# nanoSTM32.net
KiCad netlist of a schematic drawn in Altium Designer
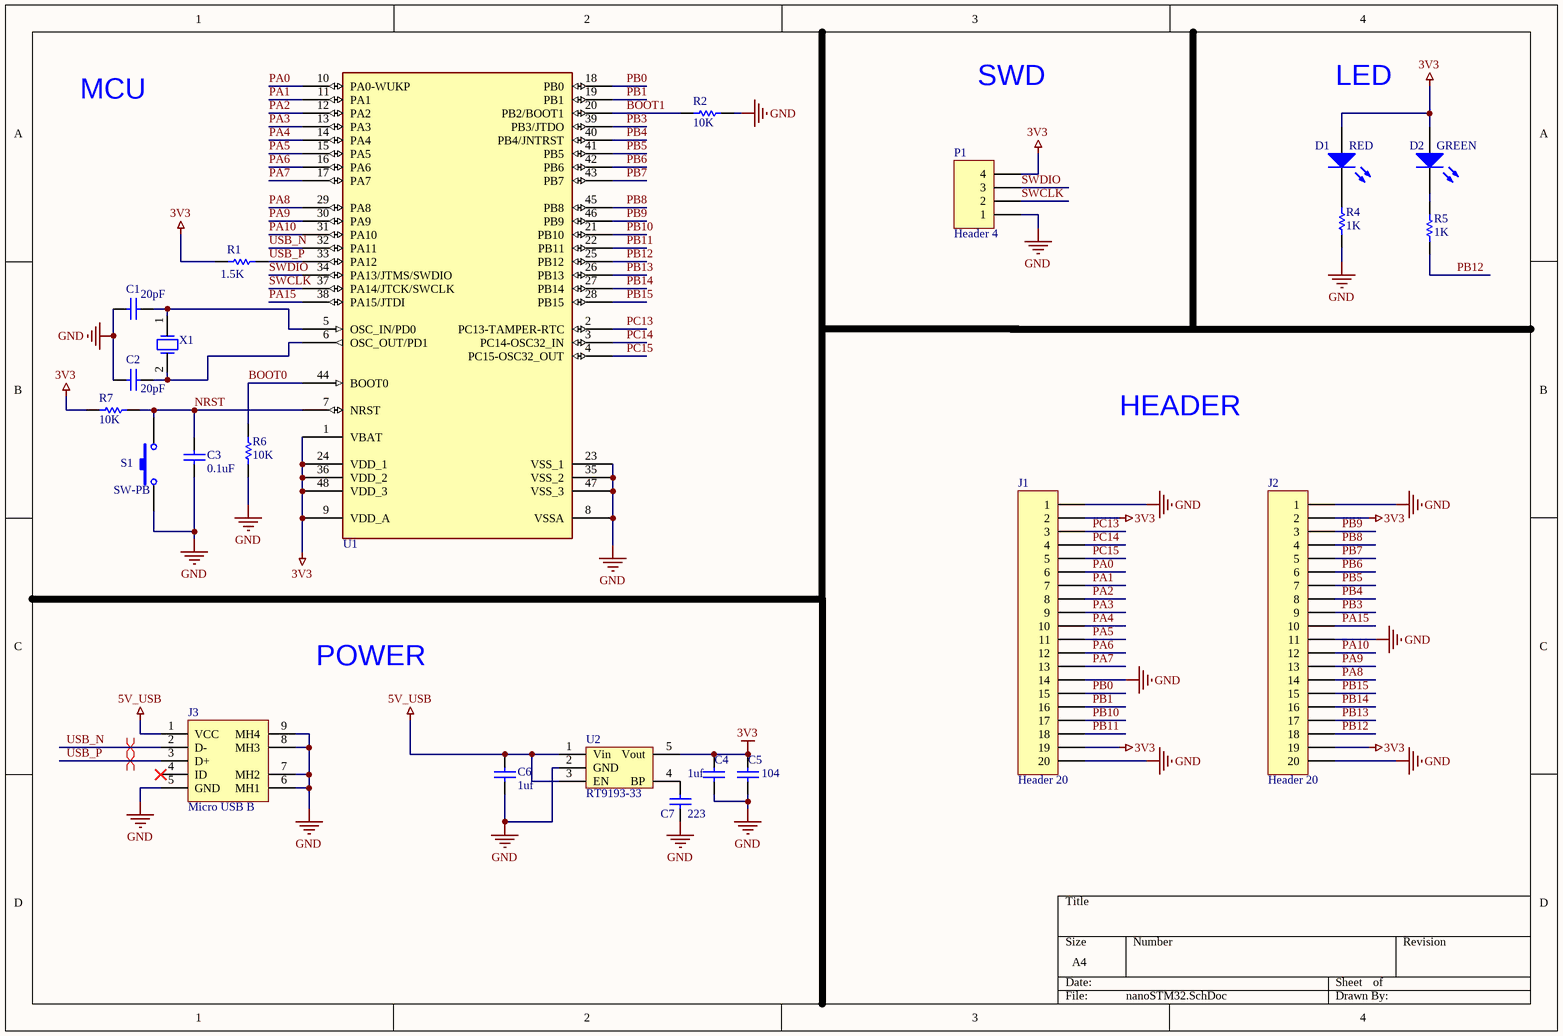
[diagram p0: nanoSTM32.SchDoc]

(export (version "E")
  (design (tool "Eeschema 10.0.6"))
  (components
    (comp (ref "C1")
      (value "20pF")
      (footprint "0603_C")
      (description "Capacitor")
      (fields (field (name "Comment") "C0603") (field (name "PUBLISHER") "Altium Limited"))
      (libsource (lib "MYLIB") (part "C-RAD-0603"))
    )
    (comp (ref "C2")
      (value "20pF")
      (footprint "0603_C")
      (description "Capacitor")
      (fields (field (name "Comment") "C0603") (field (name "PUBLISHER") "Altium Limited"))
      (libsource (lib "MYLIB") (part "C-RAD-0603"))
    )
    (comp (ref "C3")
      (value "0.1uF")
      (footprint "0603_C")
      (description "Capacitor")
      (fields (field (name "Comment") "C0603") (field (name "PUBLISHER") "Altium Limited"))
      (libsource (lib "MYLIB") (part "C-RAD-0603"))
    )
    (comp (ref "C4")
      (value "1uf")
      (footprint "0603_C")
      (description "Capacitor")
      (libsource (lib "Cheetie Integrated Library 2017") (part "CAP"))
    )
    (comp (ref "C5")
      (value "104")
      (footprint "0603_C")
      (description "Capacitor")
      (libsource (lib "Cheetie Integrated Library 2017") (part "CAP"))
    )
    (comp (ref "C6")
      (value "1uf")
      (footprint "0603_C")
      (description "Capacitor")
      (libsource (lib "Cheetie Integrated Library 2017") (part "CAP"))
    )
    (comp (ref "C7")
      (value "223")
      (footprint "0603_C")
      (description "Capacitor")
      (libsource (lib "Cheetie Integrated Library 2017") (part "CAP"))
    )
    (comp (ref "D1")
      (value "RED")
      (footprint "0603_LED")
      (description "Typical RED, GREEN, YELLOW, AMBER GaAs LED")
      (fields (field (name "PUBLISHER") "Altium Limited"))
      (libsource (lib "MYLIB") (part "D0603"))
    )
    (comp (ref "D2")
      (value "GREEN")
      (footprint "0603_LED")
      (description "Typical RED, GREEN, YELLOW, AMBER GaAs LED")
      (fields (field (name "PUBLISHER") "Altium Limited"))
      (libsource (lib "MYLIB") (part "D0603"))
    )
    (comp (ref "J1")
      (value "Header 20")
      (footprint "HEADER_20x1")
      (libsource (lib "nanoSTM32") (part "Header 20"))
    )
    (comp (ref "J2")
      (value "Header 20")
      (footprint "HEADER_20x1")
      (libsource (lib "nanoSTM32") (part "Header 20"))
    )
    (comp (ref "J3")
      (value "Micro USB B")
      (footprint "MICRO_USB")
      (libsource (lib "nanoSTM32") (part "Micro USB B"))
    )
    (comp (ref "logo") (value "logo") (libsource (lib "nanoSTM32") (part "logo")))
    (comp (ref "P1")
      (value "Header 4")
      (footprint "HEADER_4x1")
      (description "Header, 4-Pin")
      (fields (field (name "PUBLISHER") "Altium Limited"))
      (libsource (lib "Miscellaneous Connectors") (part "Header 4"))
    )
    (comp (ref "R1")
      (value "1.5K")
      (footprint "0603_R")
      (description "Resistor")
      (fields (field (name "Comment") "R0603") (field (name "PUBLISHER") "Altium Limited"))
      (libsource (lib "MYLIB") (part "0603-1"))
    )
    (comp (ref "R2")
      (value "10K")
      (footprint "0603_R")
      (description "Resistor")
      (fields (field (name "Comment") "R0603") (field (name "PUBLISHER") "Altium Limited"))
      (libsource (lib "MYLIB") (part "R0603"))
    )
    (comp (ref "R4")
      (value "1K")
      (footprint "0603_R")
      (description "Resistor")
      (fields (field (name "Comment") "R0603") (field (name "PUBLISHER") "Altium Limited"))
      (libsource (lib "MYLIB") (part "0603-1"))
    )
    (comp (ref "R5")
      (value "1K")
      (footprint "0603_R")
      (description "Resistor")
      (fields (field (name "Comment") "R0603") (field (name "PUBLISHER") "Altium Limited"))
      (libsource (lib "MYLIB") (part "0603-1"))
    )
    (comp (ref "R6")
      (value "10K")
      (footprint "0603_R")
      (description "Resistor")
      (fields (field (name "Comment") "R0603") (field (name "PUBLISHER") "Altium Limited"))
      (libsource (lib "MYLIB") (part "0603-1"))
    )
    (comp (ref "R7")
      (value "10K")
      (footprint "0603_R")
      (description "Resistor")
      (fields (field (name "Comment") "R0603") (field (name "PUBLISHER") "Altium Limited"))
      (libsource (lib "MYLIB") (part "0603-1"))
    )
    (comp (ref "S1")
      (value "SW-PB")
      (footprint "SMT_SW_PTS_820")
      (description "Switch")
      (fields (field (name "PUBLISHER") "Altium Limited"))
      (libsource (lib "Miscellaneous Devices") (part "SW-PB"))
    )
    (comp (ref "U1")
      (value "STM32F103C8T6")
      (footprint "LQFP48_N")
      (description "LowPower MCU")
      (libsource (lib "MYLIB") (part "STM32F103C8T6"))
    )
    (comp (ref "U2")
      (value "RT9193-33")
      (footprint "SOT23-5")
      (libsource (lib "Cheetie Integrated Library 2017") (part "RT9193-33"))
    )
    (comp (ref "X1") (value "XTAL") (footprint "49SMD") (libsource (lib "MYLIB") (part "XTAL")))
  )
  (nets
    (net (code "1") (name "/BOOT0") (class "Default")
      (node (ref "R6") (pin "1") (pinfunction "1_1") (pintype "passive"))
      (node (ref "U1") (pin "44") (pinfunction "BOOT0_44") (pintype "input"))
    )
    (net (code "2") (name "/BOOT1") (class "Default")
      (node (ref "R2") (pin "2") (pinfunction "2_2") (pintype "passive"))
      (node (ref "U1") (pin "20") (pinfunction "PB2/BOOT1_20") (pintype "bidirectional"))
    )
    (net (code "3") (name "/NRST") (class "Default")
      (node (ref "C3") (pin "2") (pinfunction "2_2") (pintype "passive"))
      (node (ref "R7") (pin "1") (pinfunction "1_1") (pintype "passive"))
      (node (ref "S1") (pin "2") (pinfunction "2_2") (pintype "passive"))
      (node (ref "U1") (pin "7") (pinfunction "NRST_7") (pintype "bidirectional"))
    )
    (net (code "4") (name "/PA0") (class "Default")
      (node (ref "J1") (pin "6") (pinfunction "6_6") (pintype "passive"))
      (node (ref "U1") (pin "10") (pinfunction "PA0-WUKP_10") (pintype "bidirectional"))
    )
    (net (code "5") (name "/PA1") (class "Default")
      (node (ref "J1") (pin "7") (pinfunction "7_7") (pintype "passive"))
      (node (ref "U1") (pin "11") (pinfunction "PA1_11") (pintype "bidirectional"))
    )
    (net (code "6") (name "/PA2") (class "Default")
      (node (ref "J1") (pin "8") (pinfunction "8_8") (pintype "passive"))
      (node (ref "U1") (pin "12") (pinfunction "PA2_12") (pintype "bidirectional"))
    )
    (net (code "7") (name "/PA3") (class "Default")
      (node (ref "J1") (pin "9") (pinfunction "9_9") (pintype "passive"))
      (node (ref "U1") (pin "13") (pinfunction "PA3_13") (pintype "bidirectional"))
    )
    (net (code "8") (name "/PA4") (class "Default")
      (node (ref "J1") (pin "10") (pinfunction "10_10") (pintype "passive"))
      (node (ref "U1") (pin "14") (pinfunction "PA4_14") (pintype "bidirectional"))
    )
    (net (code "9") (name "/PA5") (class "Default")
      (node (ref "J1") (pin "11") (pinfunction "11_11") (pintype "passive"))
      (node (ref "U1") (pin "15") (pinfunction "PA5_15") (pintype "bidirectional"))
    )
    (net (code "10") (name "/PA6") (class "Default")
      (node (ref "J1") (pin "12") (pinfunction "12_12") (pintype "passive"))
      (node (ref "U1") (pin "16") (pinfunction "PA6_16") (pintype "bidirectional"))
    )
    (net (code "11") (name "/PA7") (class "Default")
      (node (ref "J1") (pin "13") (pinfunction "13_13") (pintype "passive"))
      (node (ref "U1") (pin "17") (pinfunction "PA7_17") (pintype "bidirectional"))
    )
    (net (code "12") (name "/PA8") (class "Default")
      (node (ref "J2") (pin "14") (pinfunction "14_14") (pintype "passive"))
      (node (ref "U1") (pin "29") (pinfunction "PA8_29") (pintype "bidirectional"))
    )
    (net (code "13") (name "/PA9") (class "Default")
      (node (ref "J2") (pin "13") (pinfunction "13_13") (pintype "passive"))
      (node (ref "U1") (pin "30") (pinfunction "PA9_30") (pintype "bidirectional"))
    )
    (net (code "14") (name "/PA10") (class "Default")
      (node (ref "J2") (pin "12") (pinfunction "12_12") (pintype "passive"))
      (node (ref "U1") (pin "31") (pinfunction "PA10_31") (pintype "bidirectional"))
    )
    (net (code "15") (name "/PA15") (class "Default")
      (node (ref "J2") (pin "10") (pinfunction "10_10") (pintype "passive"))
      (node (ref "U1") (pin "38") (pinfunction "PA15/JTDI_38") (pintype "bidirectional"))
    )
    (net (code "16") (name "/PB0") (class "Default")
      (node (ref "J1") (pin "15") (pinfunction "15_15") (pintype "passive"))
      (node (ref "U1") (pin "18") (pinfunction "PB0_18") (pintype "bidirectional"))
    )
    (net (code "17") (name "/PB1") (class "Default")
      (node (ref "J1") (pin "16") (pinfunction "16_16") (pintype "passive"))
      (node (ref "U1") (pin "19") (pinfunction "PB1_19") (pintype "bidirectional"))
    )
    (net (code "18") (name "/PB3") (class "Default")
      (node (ref "J2") (pin "9") (pinfunction "9_9") (pintype "passive"))
      (node (ref "U1") (pin "39") (pinfunction "PB3/JTDO_39") (pintype "bidirectional"))
    )
    (net (code "19") (name "/PB4") (class "Default")
      (node (ref "J2") (pin "8") (pinfunction "8_8") (pintype "passive"))
      (node (ref "U1") (pin "40") (pinfunction "PB4/JNTRST_40") (pintype "bidirectional"))
    )
    (net (code "20") (name "/PB5") (class "Default")
      (node (ref "J2") (pin "7") (pinfunction "7_7") (pintype "passive"))
      (node (ref "U1") (pin "41") (pinfunction "PB5_41") (pintype "bidirectional"))
    )
    (net (code "21") (name "/PB6") (class "Default")
      (node (ref "J2") (pin "6") (pinfunction "6_6") (pintype "passive"))
      (node (ref "U1") (pin "42") (pinfunction "PB6_42") (pintype "bidirectional"))
    )
    (net (code "22") (name "/PB7") (class "Default")
      (node (ref "J2") (pin "5") (pinfunction "5_5") (pintype "passive"))
      (node (ref "U1") (pin "43") (pinfunction "PB7_43") (pintype "bidirectional"))
    )
    (net (code "23") (name "/PB8") (class "Default")
      (node (ref "J2") (pin "4") (pinfunction "4_4") (pintype "passive"))
      (node (ref "U1") (pin "45") (pinfunction "PB8_45") (pintype "bidirectional"))
    )
    (net (code "24") (name "/PB9") (class "Default")
      (node (ref "J2") (pin "3") (pinfunction "3_3") (pintype "passive"))
      (node (ref "U1") (pin "46") (pinfunction "PB9_46") (pintype "bidirectional"))
    )
    (net (code "25") (name "/PB10") (class "Default")
      (node (ref "J1") (pin "17") (pinfunction "17_17") (pintype "passive"))
      (node (ref "U1") (pin "21") (pinfunction "PB10_21") (pintype "bidirectional"))
    )
    (net (code "26") (name "/PB11") (class "Default")
      (node (ref "J1") (pin "18") (pinfunction "18_18") (pintype "passive"))
      (node (ref "U1") (pin "22") (pinfunction "PB11_22") (pintype "bidirectional"))
    )
    (net (code "27") (name "/PB12") (class "Default")
      (node (ref "J2") (pin "18") (pinfunction "18_18") (pintype "passive"))
      (node (ref "R5") (pin "1") (pinfunction "1_1") (pintype "passive"))
      (node (ref "U1") (pin "25") (pinfunction "PB12_25") (pintype "bidirectional"))
    )
    (net (code "28") (name "/PB13") (class "Default")
      (node (ref "J2") (pin "17") (pinfunction "17_17") (pintype "passive"))
      (node (ref "U1") (pin "26") (pinfunction "PB13_26") (pintype "bidirectional"))
    )
    (net (code "29") (name "/PB14") (class "Default")
      (node (ref "J2") (pin "16") (pinfunction "16_16") (pintype "passive"))
      (node (ref "U1") (pin "27") (pinfunction "PB14_27") (pintype "bidirectional"))
    )
    (net (code "30") (name "/PB15") (class "Default")
      (node (ref "J2") (pin "15") (pinfunction "15_15") (pintype "passive"))
      (node (ref "U1") (pin "28") (pinfunction "PB15_28") (pintype "bidirectional"))
    )
    (net (code "31") (name "/PC13") (class "Default")
      (node (ref "J1") (pin "3") (pinfunction "3_3") (pintype "passive"))
      (node (ref "U1") (pin "2") (pinfunction "PC13-TAMPER-RTC_2") (pintype "bidirectional"))
    )
    (net (code "32") (name "/PC14") (class "Default")
      (node (ref "J1") (pin "4") (pinfunction "4_4") (pintype "passive"))
      (node (ref "U1") (pin "3") (pinfunction "PC14-OSC32_IN_3") (pintype "bidirectional"))
    )
    (net (code "33") (name "/PC15") (class "Default")
      (node (ref "J1") (pin "5") (pinfunction "5_5") (pintype "passive"))
      (node (ref "U1") (pin "4") (pinfunction "PC15-OSC32_OUT_4") (pintype "bidirectional"))
    )
    (net (code "34") (name "/SWCLK") (class "Default")
      (node (ref "P1") (pin "2") (pinfunction "2_2") (pintype "passive"))
      (node (ref "U1") (pin "37") (pinfunction "PA14/JTCK/SWCLK_37") (pintype "bidirectional"))
    )
    (net (code "35") (name "/SWDIO") (class "Default")
      (node (ref "P1") (pin "3") (pinfunction "3_3") (pintype "passive"))
      (node (ref "U1") (pin "34") (pinfunction "PA13/JTMS/SWDIO_34") (pintype "bidirectional"))
    )
    (net (code "36") (name "/USB_N") (class "Default")
      (node (ref "J3") (pin "2") (pinfunction "D-_2") (pintype "passive"))
      (node (ref "U1") (pin "32") (pinfunction "PA11_32") (pintype "bidirectional"))
    )
    (net (code "37") (name "/USB_P") (class "Default")
      (node (ref "J3") (pin "3") (pinfunction "D+_3") (pintype "passive"))
      (node (ref "R1") (pin "1") (pinfunction "1_1") (pintype "passive"))
      (node (ref "U1") (pin "33") (pinfunction "PA12_33") (pintype "bidirectional"))
    )
    (net (code "38") (name "3V3") (class "Default")
      (node (ref "C4") (pin "2") (pinfunction "2_2") (pintype "passive"))
      (node (ref "C5") (pin "2") (pinfunction "2_2") (pintype "passive"))
      (node (ref "D1") (pin "1") (pinfunction "A_1") (pintype "passive"))
      (node (ref "D2") (pin "1") (pinfunction "A_1") (pintype "passive"))
      (node (ref "J1") (pin "19") (pinfunction "19_19") (pintype "passive"))
      (node (ref "J1") (pin "2") (pinfunction "2_2") (pintype "passive"))
      (node (ref "J2") (pin "19") (pinfunction "19_19") (pintype "passive"))
      (node (ref "J2") (pin "2") (pinfunction "2_2") (pintype "passive"))
      (node (ref "P1") (pin "4") (pinfunction "4_4") (pintype "passive"))
      (node (ref "R1") (pin "2") (pinfunction "2_2") (pintype "passive"))
      (node (ref "R7") (pin "2") (pinfunction "2_2") (pintype "passive"))
      (node (ref "U1") (pin "1") (pinfunction "VBAT_1") (pintype "passive"))
      (node (ref "U1") (pin "24") (pinfunction "VDD_1_24") (pintype "passive"))
      (node (ref "U1") (pin "36") (pinfunction "VDD_2_36") (pintype "passive"))
      (node (ref "U1") (pin "48") (pinfunction "VDD_3_48") (pintype "passive"))
      (node (ref "U1") (pin "9") (pinfunction "VDD_A_9") (pintype "passive"))
      (node (ref "U2") (pin "5") (pinfunction "Vout_5") (pintype "passive"))
    )
    (net (code "39") (name "5V_USB") (class "Default")
      (node (ref "C6") (pin "2") (pinfunction "2_2") (pintype "passive"))
      (node (ref "J3") (pin "1") (pinfunction "VCC_1") (pintype "passive"))
      (node (ref "U2") (pin "1") (pinfunction "Vin_1") (pintype "passive"))
      (node (ref "U2") (pin "3") (pinfunction "EN_3") (pintype "passive"))
    )
    (net (code "40") (name "GND") (class "Default")
      (node (ref "C1") (pin "2") (pinfunction "2_2") (pintype "passive"))
      (node (ref "C2") (pin "2") (pinfunction "2_2") (pintype "passive"))
      (node (ref "C3") (pin "1") (pinfunction "1_1") (pintype "passive"))
      (node (ref "C4") (pin "1") (pinfunction "1_1") (pintype "passive"))
      (node (ref "C5") (pin "1") (pinfunction "1_1") (pintype "passive"))
      (node (ref "C6") (pin "1") (pinfunction "1_1") (pintype "passive"))
      (node (ref "C7") (pin "1") (pinfunction "1_1") (pintype "passive"))
      (node (ref "J1") (pin "1") (pinfunction "1_1") (pintype "passive"))
      (node (ref "J1") (pin "14") (pinfunction "14_14") (pintype "passive"))
      (node (ref "J1") (pin "20") (pinfunction "20_20") (pintype "passive"))
      (node (ref "J2") (pin "1") (pinfunction "1_1") (pintype "passive"))
      (node (ref "J2") (pin "11") (pinfunction "11_11") (pintype "passive"))
      (node (ref "J2") (pin "20") (pinfunction "20_20") (pintype "passive"))
      (node (ref "J3") (pin "5") (pinfunction "GND_5") (pintype "passive"))
      (node (ref "J3") (pin "6") (pinfunction "MH1_6") (pintype "passive"))
      (node (ref "J3") (pin "7") (pinfunction "MH2_7") (pintype "passive"))
      (node (ref "J3") (pin "8") (pinfunction "MH3_8") (pintype "passive"))
      (node (ref "J3") (pin "9") (pinfunction "MH4_9") (pintype "passive"))
      (node (ref "P1") (pin "1") (pinfunction "1_1") (pintype "passive"))
      (node (ref "R2") (pin "1") (pinfunction "1_1") (pintype "passive"))
      (node (ref "R4") (pin "1") (pinfunction "1_1") (pintype "passive"))
      (node (ref "R6") (pin "2") (pinfunction "2_2") (pintype "passive"))
      (node (ref "S1") (pin "1") (pinfunction "1_1") (pintype "passive"))
      (node (ref "U1") (pin "23") (pinfunction "VSS_1_23") (pintype "passive"))
      (node (ref "U1") (pin "35") (pinfunction "VSS_2_35") (pintype "passive"))
      (node (ref "U1") (pin "47") (pinfunction "VSS_3_47") (pintype "passive"))
      (node (ref "U1") (pin "8") (pinfunction "VSSA_8") (pintype "passive"))
      (node (ref "U2") (pin "2") (pinfunction "GND_2") (pintype "passive"))
    )
    (net (code "41") (name "Net-(D1-K)") (class "Default")
      (node (ref "D1") (pin "2") (pinfunction "K_2") (pintype "passive"))
      (node (ref "R4") (pin "2") (pinfunction "2_2") (pintype "passive"))
    )
    (net (code "42") (name "Net-(D2-K)") (class "Default")
      (node (ref "D2") (pin "2") (pinfunction "K_2") (pintype "passive"))
      (node (ref "R5") (pin "2") (pinfunction "2_2") (pintype "passive"))
    )
    (net (code "43") (name "Net-(U1-OSC_IN{slash}PD0)") (class "Default")
      (node (ref "C1") (pin "1") (pinfunction "1_1") (pintype "passive"))
      (node (ref "U1") (pin "5") (pinfunction "OSC_IN/PD0_5") (pintype "input"))
      (node (ref "X1") (pin "1") (pinfunction "1_1") (pintype "passive"))
    )
    (net (code "44") (name "Net-(U1-OSC_OUT{slash}PD1)") (class "Default")
      (node (ref "C2") (pin "1") (pinfunction "1_1") (pintype "passive"))
      (node (ref "U1") (pin "6") (pinfunction "OSC_OUT/PD1_6") (pintype "output"))
      (node (ref "X1") (pin "2") (pinfunction "2_2") (pintype "passive"))
    )
    (net (code "45") (name "Net-(U2-BP)") (class "Default")
      (node (ref "C7") (pin "2") (pinfunction "2_2") (pintype "passive"))
      (node (ref "U2") (pin "4") (pinfunction "BP_4") (pintype "passive"))
    )
    (net (code "46") (name "unconnected-(J3-ID-Pad4)") (class "Default")
      (node (ref "J3") (pin "4") (pinfunction "ID_4") (pintype "passive+no_connect"))
    )
  )
)
